# SCH_IMU_4connectors_antiCW.net
KiCad netlist of a schematic drawn in EasyEDA
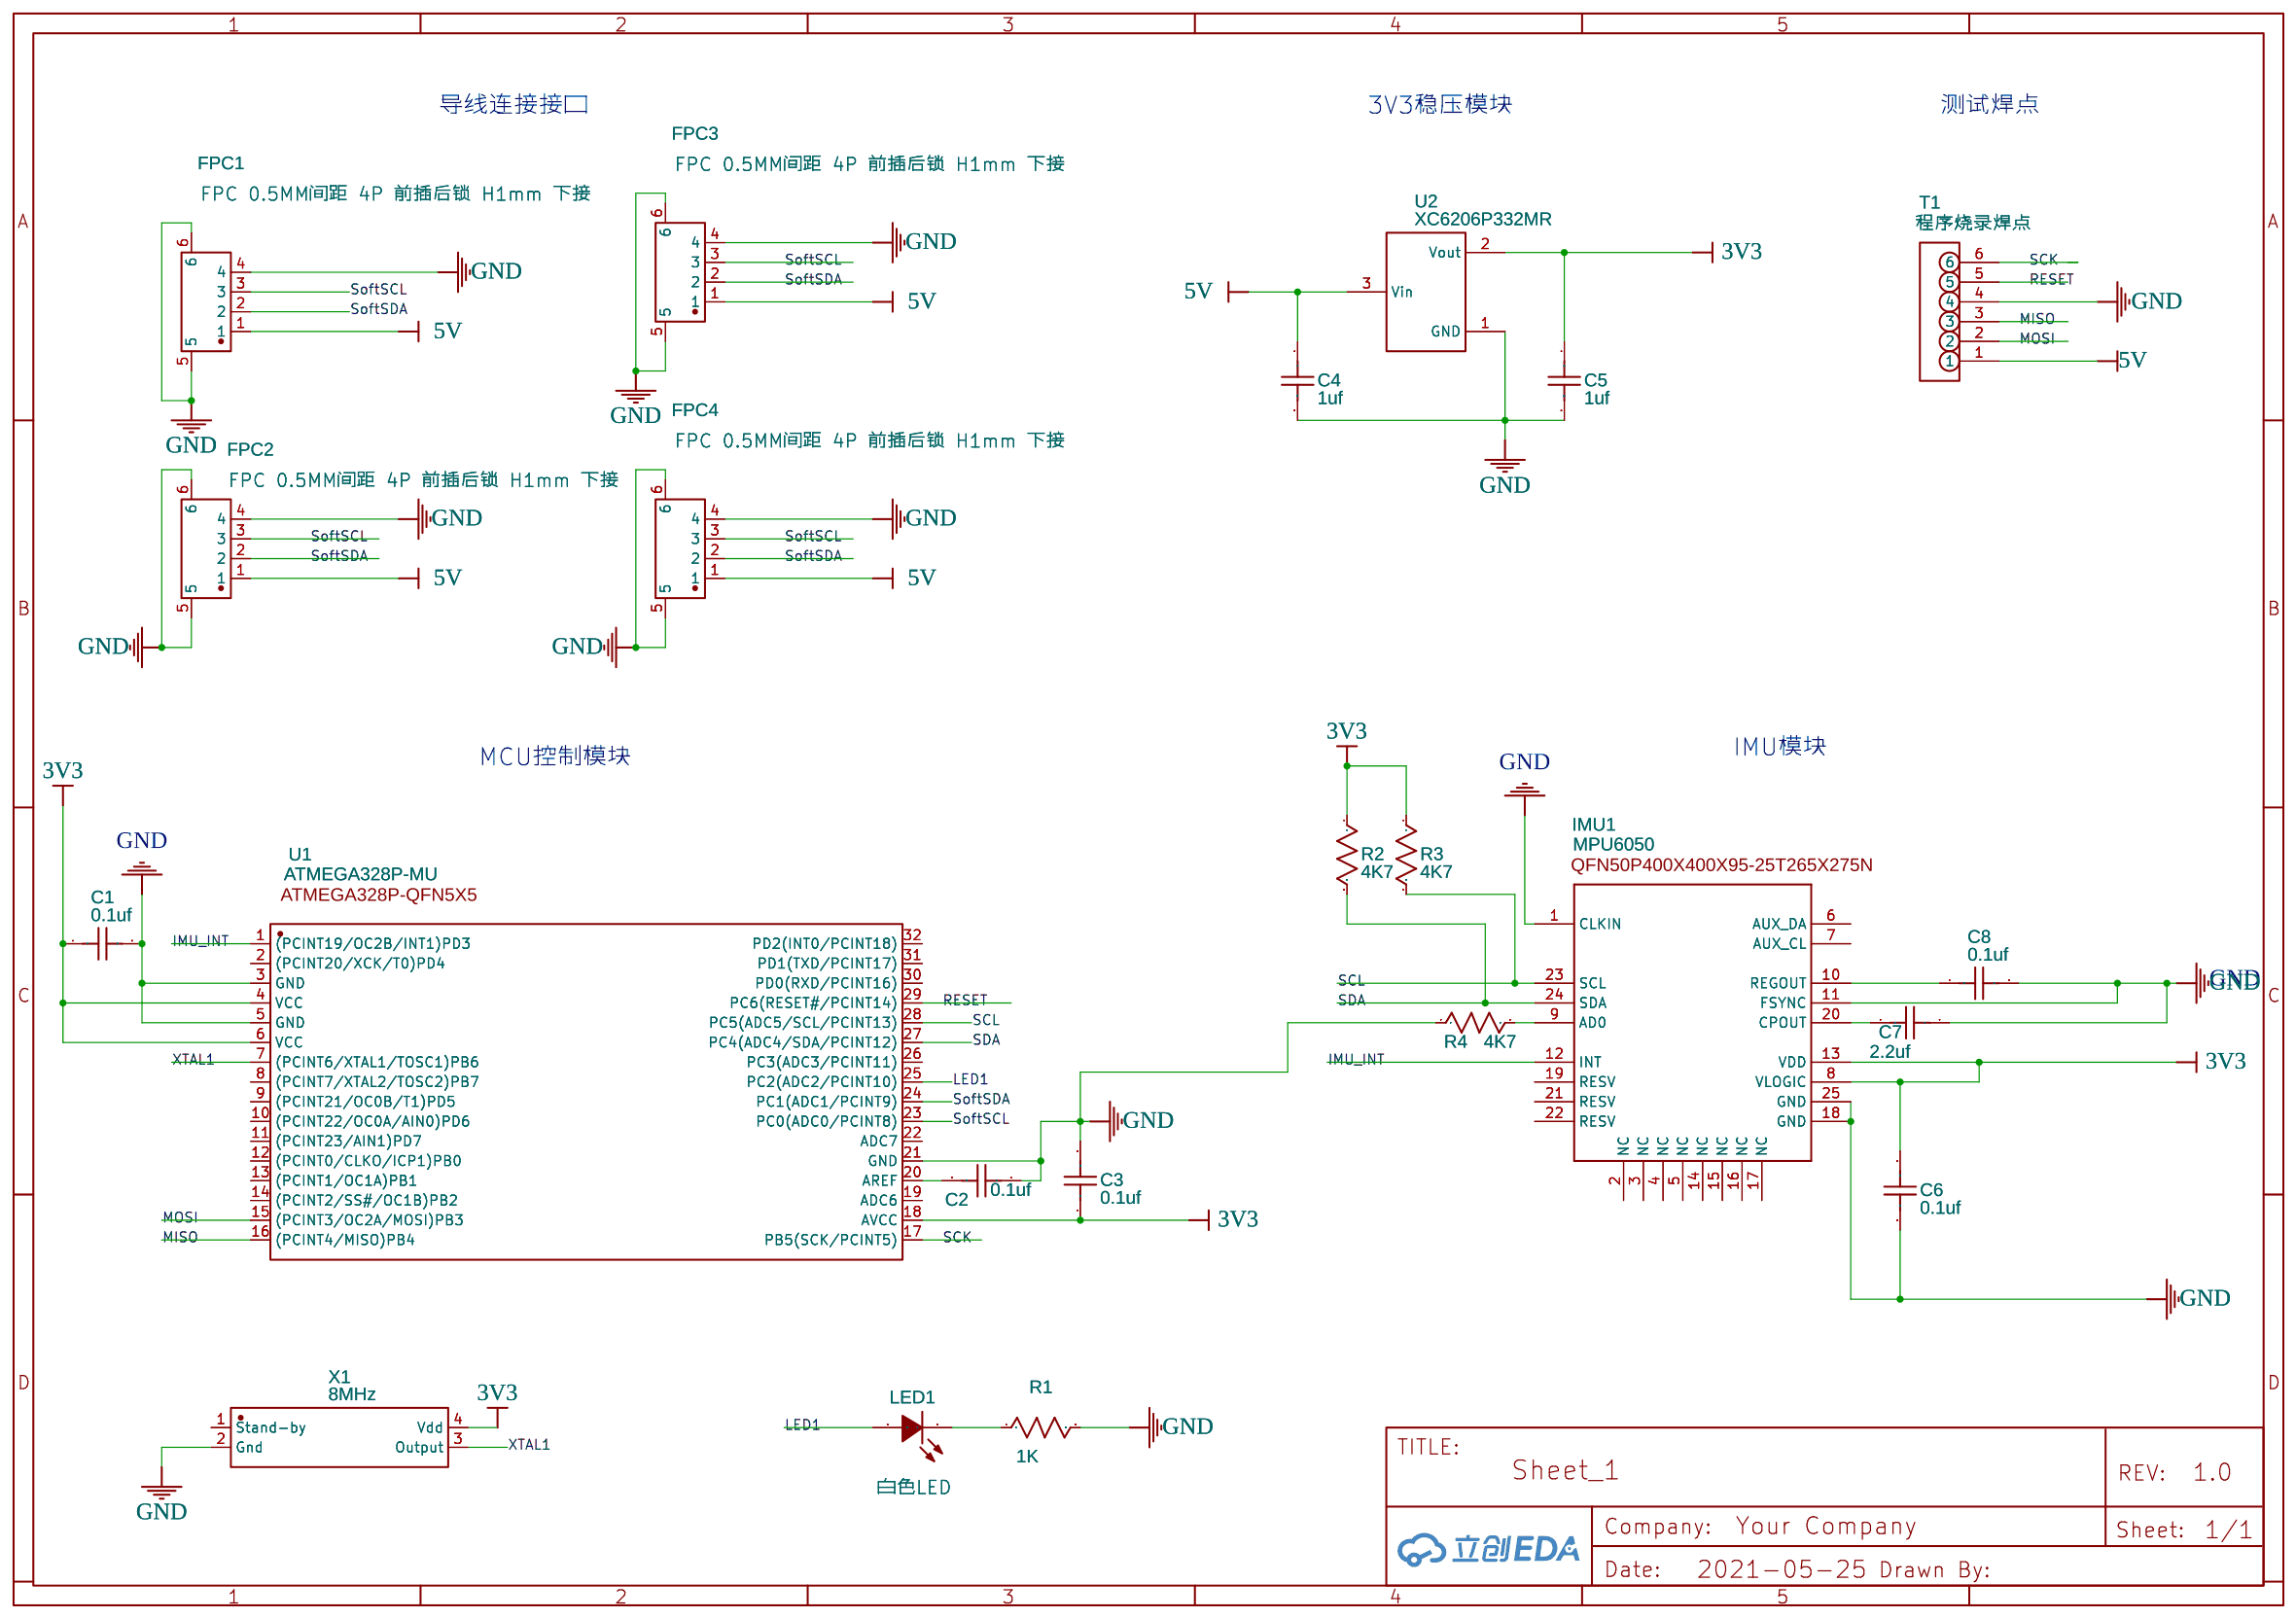
[diagram p0: schematic sheet]

(export (version "E")
  (design (tool "Eeschema 10.0.6"))
  (components
    (comp (ref "C1") (value "0.1uf") (libsource (lib "") (part "C_0402_US_2")))
    (comp (ref "C2") (value "0.1uf") (libsource (lib "") (part "C_0402_US_1")))
    (comp (ref "C3") (value "0.1uf") (libsource (lib "") (part "C_0402_US_3")))
    (comp (ref "C4") (value "1uf") (libsource (lib "") (part "C_0402_US")))
    (comp (ref "C5") (value "1uf") (libsource (lib "") (part "C_0402_US")))
    (comp (ref "C6") (value "0.1uf") (libsource (lib "") (part "C_0402_US")))
    (comp (ref "C7") (value "2.2uf") (libsource (lib "") (part "C_0402_US_1")))
    (comp (ref "C8") (value "0.1uf") (libsource (lib "") (part "C_0402_US_2")))
    (comp (ref "FPC1")
      (value "FPC 0.5MM间距 4P 前插后锁 H1mm 下接")
      (fields
        (field (name "BOM_Manufacturer Part") "FPC 0.5MM 4P 翻盖式 H2.0")
        (field (name "BOM_Supplier Part") "C9345")
      )
      (libsource (lib "") (part "FPC 0.5MM 4P 翻盖式 H2.0"))
    )
    (comp (ref "FPC2")
      (value "FPC 0.5MM间距 4P 前插后锁 H1mm 下接")
      (fields
        (field (name "BOM_Manufacturer Part") "FPC 0.5MM 4P 翻盖式 H2.0")
        (field (name "BOM_Supplier Part") "C9345")
      )
      (libsource (lib "") (part "FPC 0.5MM 4P 翻盖式 H2.0"))
    )
    (comp (ref "FPC3")
      (value "FPC 0.5MM间距 4P 前插后锁 H1mm 下接")
      (fields
        (field (name "BOM_Manufacturer Part") "FPC 0.5MM 4P 翻盖式 H2.0")
        (field (name "BOM_Supplier Part") "C9345")
      )
      (libsource (lib "") (part "FPC 0.5MM 4P 翻盖式 H2.0"))
    )
    (comp (ref "FPC4")
      (value "FPC 0.5MM间距 4P 前插后锁 H1mm 下接")
      (fields
        (field (name "BOM_Manufacturer Part") "FPC 0.5MM 4P 翻盖式 H2.0")
        (field (name "BOM_Supplier Part") "C9345")
      )
      (libsource (lib "") (part "FPC 0.5MM 4P 翻盖式 H2.0"))
    )
    (comp (ref "IMU1") (value "MPU6050") (libsource (lib "") (part "MPU6050")))
    (comp (ref "LED1")
      (value "白色LED")
      (fields
        (field (name "BOM_Manufacturer Part") "19-217/BHC-XL2M2TY/3T")
        (field (name "BOM_Supplier Part") "C264464")
      )
      (libsource (lib "") (part "19-217/BHC-XL2M2TY/3T"))
    )
    (comp (ref "R1") (value "1K") (libsource (lib "") (part "R_0402_US_1")))
    (comp (ref "R2") (value "4K7") (libsource (lib "") (part "R_0402_US")))
    (comp (ref "R3") (value "4K7") (libsource (lib "") (part "R_0402_US")))
    (comp (ref "R4") (value "4K7") (libsource (lib "") (part "R_0402_US_1")))
    (comp (ref "T1") (value "程序烧录焊点") (libsource (lib "") (part "Test")))
    (comp (ref "U1")
      (value "ATMEGA328P-MU")
      (fields
        (field (name "BOM_Manufacturer Part") "ATMEGA328P-AU")
        (field (name "BOM_Supplier Part") "C14877")
      )
      (libsource (lib "") (part "ATMEGA328P-AU"))
    )
    (comp (ref "U2")
      (value "XC6206P332MR")
      (fields (field (name "BOM_Supplier Part") "C5446"))
      (libsource (lib "") (part "XC6206P332MR"))
    )
    (comp (ref "X1")
      (value "8MHz")
      (fields
        (field (name "BOM_Manufacturer Part") "ECS-1612MV-080-CN-TR")
        (field (name "BOM_Supplier Part") "C405436")
      )
      (libsource (lib "") (part "ECS-1612MV-080-CN-TR"))
    )
  )
  (nets
    (net (code "1") (name "/IMU_INT") (class "Default")
      (node (ref "IMU1") (pin "12") (pinfunction "INT_12") (pintype "unspecified"))
      (node (ref "U1") (pin "1") (pinfunction "(PCINT19/OC2B/INT1)PD3_1") (pintype "unspecified"))
    )
    (net (code "2") (name "/LED1") (class "Default")
      (node (ref "LED1") (pin "1") (pinfunction "A_1") (pintype "unspecified"))
      (node (ref "U1") (pin "25") (pinfunction "PC2(ADC2/PCINT10)_25") (pintype "unspecified"))
    )
    (net (code "3") (name "/MISO") (class "Default")
      (node (ref "T1") (pin "3") (pinfunction "3_3") (pintype "unspecified"))
      (node (ref "U1") (pin "16") (pinfunction "(PCINT4/MISO)PB4_16") (pintype "unspecified"))
    )
    (net (code "4") (name "/MOSI") (class "Default")
      (node (ref "T1") (pin "2") (pinfunction "2_2") (pintype "unspecified"))
      (node (ref "U1") (pin "15") (pinfunction "(PCINT3/OC2A/MOSI)PB3_15") (pintype "unspecified"))
    )
    (net (code "5") (name "/RESET") (class "Default")
      (node (ref "T1") (pin "5") (pinfunction "5_5") (pintype "unspecified"))
      (node (ref "U1") (pin "29") (pinfunction "PC6(RESET#/PCINT14)_29") (pintype "unspecified"))
    )
    (net (code "6") (name "/SCK") (class "Default")
      (node (ref "T1") (pin "6") (pinfunction "6_6") (pintype "unspecified"))
      (node (ref "U1") (pin "17") (pinfunction "PB5(SCK/PCINT5)_17") (pintype "unspecified"))
    )
    (net (code "7") (name "/SCL") (class "Default")
      (node (ref "IMU1") (pin "23") (pinfunction "SCL_23") (pintype "input"))
      (node (ref "R3") (pin "2") (pinfunction "2_2") (pintype "unspecified"))
      (node (ref "U1") (pin "28") (pinfunction "PC5(ADC5/SCL/PCINT13)_28") (pintype "unspecified"))
    )
    (net (code "8") (name "/SDA") (class "Default")
      (node (ref "IMU1") (pin "24") (pinfunction "SDA_24") (pintype "unspecified"))
      (node (ref "R2") (pin "2") (pinfunction "2_2") (pintype "unspecified"))
      (node (ref "U1") (pin "27") (pinfunction "PC4(ADC4/SDA/PCINT12)_27") (pintype "unspecified"))
    )
    (net (code "9") (name "/SoftSCL") (class "Default")
      (node (ref "FPC1") (pin "3") (pinfunction "3_3") (pintype "unspecified"))
      (node (ref "FPC2") (pin "3") (pinfunction "3_3") (pintype "unspecified"))
      (node (ref "FPC3") (pin "3") (pinfunction "3_3") (pintype "unspecified"))
      (node (ref "FPC4") (pin "3") (pinfunction "3_3") (pintype "unspecified"))
      (node (ref "U1") (pin "23") (pinfunction "PC0(ADC0/PCINT8)_23") (pintype "unspecified"))
    )
    (net (code "10") (name "/SoftSDA") (class "Default")
      (node (ref "FPC1") (pin "2") (pinfunction "2_2") (pintype "unspecified"))
      (node (ref "FPC2") (pin "2") (pinfunction "2_2") (pintype "unspecified"))
      (node (ref "FPC3") (pin "2") (pinfunction "2_2") (pintype "unspecified"))
      (node (ref "FPC4") (pin "2") (pinfunction "2_2") (pintype "unspecified"))
      (node (ref "U1") (pin "24") (pinfunction "PC1(ADC1/PCINT9)_24") (pintype "unspecified"))
    )
    (net (code "11") (name "/XTAL1") (class "Default")
      (node (ref "U1") (pin "7") (pinfunction "(PCINT6/XTAL1/TOSC1)PB6_7") (pintype "unspecified"))
      (node (ref "X1") (pin "3") (pinfunction "Output_3") (pintype "unspecified"))
    )
    (net (code "12") (name "3V3") (class "Default")
      (node (ref "C1") (pin "1") (pinfunction "1_1") (pintype "unspecified"))
      (node (ref "C3") (pin "1") (pinfunction "1_1") (pintype "unspecified"))
      (node (ref "C5") (pin "1") (pinfunction "1_1") (pintype "unspecified"))
      (node (ref "C6") (pin "1") (pinfunction "1_1") (pintype "unspecified"))
      (node (ref "IMU1") (pin "13") (pinfunction "VDD_13") (pintype "passive"))
      (node (ref "IMU1") (pin "8") (pinfunction "VLOGIC_8") (pintype "passive"))
      (node (ref "R2") (pin "1") (pinfunction "1_1") (pintype "unspecified"))
      (node (ref "R3") (pin "1") (pinfunction "1_1") (pintype "unspecified"))
      (node (ref "U1") (pin "18") (pinfunction "AVCC_18") (pintype "unspecified"))
      (node (ref "U1") (pin "4") (pinfunction "VCC_4") (pintype "unspecified"))
      (node (ref "U1") (pin "6") (pinfunction "VCC_6") (pintype "unspecified"))
      (node (ref "U2") (pin "2") (pinfunction "Vout_2") (pintype "unspecified"))
      (node (ref "X1") (pin "4") (pinfunction "Vdd_4") (pintype "unspecified"))
    )
    (net (code "13") (name "5V") (class "Default")
      (node (ref "C4") (pin "1") (pinfunction "1_1") (pintype "unspecified"))
      (node (ref "FPC1") (pin "1") (pinfunction "1_1") (pintype "unspecified"))
      (node (ref "FPC2") (pin "1") (pinfunction "1_1") (pintype "unspecified"))
      (node (ref "FPC3") (pin "1") (pinfunction "1_1") (pintype "unspecified"))
      (node (ref "FPC4") (pin "1") (pinfunction "1_1") (pintype "unspecified"))
      (node (ref "T1") (pin "1") (pinfunction "1_1") (pintype "unspecified"))
      (node (ref "U2") (pin "3") (pinfunction "Vin_3") (pintype "unspecified"))
    )
    (net (code "14") (name "GND") (class "Default")
      (node (ref "C1") (pin "2") (pinfunction "2_2") (pintype "unspecified"))
      (node (ref "C2") (pin "1") (pinfunction "1_1") (pintype "unspecified"))
      (node (ref "C3") (pin "2") (pinfunction "2_2") (pintype "unspecified"))
      (node (ref "C4") (pin "2") (pinfunction "2_2") (pintype "unspecified"))
      (node (ref "C5") (pin "2") (pinfunction "2_2") (pintype "unspecified"))
      (node (ref "C6") (pin "2") (pinfunction "2_2") (pintype "unspecified"))
      (node (ref "C7") (pin "1") (pinfunction "1_1") (pintype "unspecified"))
      (node (ref "C8") (pin "2") (pinfunction "2_2") (pintype "unspecified"))
      (node (ref "FPC1") (pin "4") (pinfunction "4_4") (pintype "unspecified"))
      (node (ref "FPC1") (pin "5") (pinfunction "5_5") (pintype "unspecified"))
      (node (ref "FPC1") (pin "6") (pinfunction "6_6") (pintype "unspecified"))
      (node (ref "FPC2") (pin "4") (pinfunction "4_4") (pintype "unspecified"))
      (node (ref "FPC2") (pin "5") (pinfunction "5_5") (pintype "unspecified"))
      (node (ref "FPC2") (pin "6") (pinfunction "6_6") (pintype "unspecified"))
      (node (ref "FPC3") (pin "4") (pinfunction "4_4") (pintype "unspecified"))
      (node (ref "FPC3") (pin "5") (pinfunction "5_5") (pintype "unspecified"))
      (node (ref "FPC3") (pin "6") (pinfunction "6_6") (pintype "unspecified"))
      (node (ref "FPC4") (pin "4") (pinfunction "4_4") (pintype "unspecified"))
      (node (ref "FPC4") (pin "5") (pinfunction "5_5") (pintype "unspecified"))
      (node (ref "FPC4") (pin "6") (pinfunction "6_6") (pintype "unspecified"))
      (node (ref "IMU1") (pin "1") (pinfunction "CLKIN_1") (pintype "input"))
      (node (ref "IMU1") (pin "11") (pinfunction "FSYNC_11") (pintype "input"))
      (node (ref "IMU1") (pin "18") (pinfunction "GND_18") (pintype "passive"))
      (node (ref "IMU1") (pin "25") (pinfunction "GND_25") (pintype "passive"))
      (node (ref "R1") (pin "2") (pinfunction "2_2") (pintype "unspecified"))
      (node (ref "R4") (pin "1") (pinfunction "1_1") (pintype "unspecified"))
      (node (ref "T1") (pin "4") (pinfunction "4_4") (pintype "unspecified"))
      (node (ref "U1") (pin "21") (pinfunction "GND_21") (pintype "unspecified"))
      (node (ref "U1") (pin "3") (pinfunction "GND_3") (pintype "unspecified"))
      (node (ref "U1") (pin "5") (pinfunction "GND_5") (pintype "unspecified"))
      (node (ref "U2") (pin "1") (pinfunction "GND_1") (pintype "unspecified"))
      (node (ref "X1") (pin "2") (pinfunction "Gnd_2") (pintype "unspecified"))
    )
    (net (code "15") (name "Net-(IMU1-AD0)") (class "Default")
      (node (ref "IMU1") (pin "9") (pinfunction "AD0_9") (pintype "input"))
      (node (ref "R4") (pin "2") (pinfunction "2_2") (pintype "unspecified"))
    )
    (net (code "16") (name "Net-(IMU1-CPOUT)") (class "Default")
      (node (ref "C7") (pin "2") (pinfunction "2_2") (pintype "unspecified"))
      (node (ref "IMU1") (pin "20") (pinfunction "CPOUT_20") (pintype "output"))
    )
    (net (code "17") (name "Net-(IMU1-REGOUT)") (class "Default")
      (node (ref "C8") (pin "1") (pinfunction "1_1") (pintype "unspecified"))
      (node (ref "IMU1") (pin "10") (pinfunction "REGOUT_10") (pintype "output"))
    )
    (net (code "18") (name "Net-(LED1-K)") (class "Default")
      (node (ref "LED1") (pin "2") (pinfunction "K_2") (pintype "unspecified"))
      (node (ref "R1") (pin "1") (pinfunction "1_1") (pintype "unspecified"))
    )
    (net (code "19") (name "Net-(U1-AREF)") (class "Default")
      (node (ref "C2") (pin "2") (pinfunction "2_2") (pintype "unspecified"))
      (node (ref "U1") (pin "20") (pinfunction "AREF_20") (pintype "unspecified"))
    )
    (net (code "20") (name "unconnected-(IMU1-AUX_CL-Pad7)") (class "Default")
      (node (ref "IMU1") (pin "7") (pinfunction "AUX_CL_7") (pintype "unspecified"))
    )
    (net (code "21") (name "unconnected-(IMU1-AUX_DA-Pad6)") (class "Default")
      (node (ref "IMU1") (pin "6") (pinfunction "AUX_DA_6") (pintype "unspecified"))
    )
    (net (code "22") (name "unconnected-(IMU1-NC-Pad2)") (class "Default")
      (node (ref "IMU1") (pin "2") (pinfunction "NC_2") (pintype "unspecified"))
    )
    (net (code "23") (name "unconnected-(IMU1-NC-Pad3)") (class "Default")
      (node (ref "IMU1") (pin "3") (pinfunction "NC_3") (pintype "unspecified"))
    )
    (net (code "24") (name "unconnected-(IMU1-NC-Pad4)") (class "Default")
      (node (ref "IMU1") (pin "4") (pinfunction "NC_4") (pintype "unspecified"))
    )
    (net (code "25") (name "unconnected-(IMU1-NC-Pad5)") (class "Default")
      (node (ref "IMU1") (pin "5") (pinfunction "NC_5") (pintype "unspecified"))
    )
    (net (code "26") (name "unconnected-(IMU1-NC-Pad14)") (class "Default")
      (node (ref "IMU1") (pin "14") (pinfunction "NC_14") (pintype "unspecified"))
    )
    (net (code "27") (name "unconnected-(IMU1-NC-Pad15)") (class "Default")
      (node (ref "IMU1") (pin "15") (pinfunction "NC_15") (pintype "unspecified"))
    )
    (net (code "28") (name "unconnected-(IMU1-NC-Pad16)") (class "Default")
      (node (ref "IMU1") (pin "16") (pinfunction "NC_16") (pintype "unspecified"))
    )
    (net (code "29") (name "unconnected-(IMU1-NC-Pad17)") (class "Default")
      (node (ref "IMU1") (pin "17") (pinfunction "NC_17") (pintype "unspecified"))
    )
    (net (code "30") (name "unconnected-(IMU1-RESV-Pad19)") (class "Default")
      (node (ref "IMU1") (pin "19") (pinfunction "RESV_19") (pintype "unspecified"))
    )
    (net (code "31") (name "unconnected-(IMU1-RESV-Pad21)") (class "Default")
      (node (ref "IMU1") (pin "21") (pinfunction "RESV_21") (pintype "unspecified"))
    )
    (net (code "32") (name "unconnected-(IMU1-RESV-Pad22)") (class "Default")
      (node (ref "IMU1") (pin "22") (pinfunction "RESV_22") (pintype "unspecified"))
    )
    (net (code "33") (name "unconnected-(U1-(PCINT0{slash}CLKO{slash}ICP1)PB0-Pad12)") (class "Default")
      (node (ref "U1") (pin "12") (pinfunction "(PCINT0/CLKO/ICP1)PB0_12") (pintype "unspecified"))
    )
    (net (code "34") (name "unconnected-(U1-(PCINT1{slash}OC1A)PB1-Pad13)") (class "Default")
      (node (ref "U1") (pin "13") (pinfunction "(PCINT1/OC1A)PB1_13") (pintype "unspecified"))
    )
    (net (code "35") (name "unconnected-(U1-(PCINT2{slash}SS#{slash}OC1B)PB2-Pad14)") (class "Default")
      (node (ref "U1") (pin "14") (pinfunction "(PCINT2/SS#/OC1B)PB2_14") (pintype "unspecified"))
    )
    (net (code "36") (name "unconnected-(U1-(PCINT7{slash}XTAL2{slash}TOSC2)PB7-Pad8)") (class "Default")
      (node (ref "U1") (pin "8") (pinfunction "(PCINT7/XTAL2/TOSC2)PB7_8") (pintype "unspecified"))
    )
    (net (code "37") (name "unconnected-(U1-(PCINT20{slash}XCK{slash}T0)PD4-Pad2)") (class "Default")
      (node (ref "U1") (pin "2") (pinfunction "(PCINT20/XCK/T0)PD4_2") (pintype "unspecified"))
    )
    (net (code "38") (name "unconnected-(U1-(PCINT21{slash}OC0B{slash}T1)PD5-Pad9)") (class "Default")
      (node (ref "U1") (pin "9") (pinfunction "(PCINT21/OC0B/T1)PD5_9") (pintype "unspecified"))
    )
    (net (code "39") (name "unconnected-(U1-(PCINT22{slash}OC0A{slash}AIN0)PD6-Pad10)") (class "Default")
      (node (ref "U1") (pin "10") (pinfunction "(PCINT22/OC0A/AIN0)PD6_10") (pintype "unspecified"))
    )
    (net (code "40") (name "unconnected-(U1-(PCINT23{slash}AIN1)PD7-Pad11)") (class "Default")
      (node (ref "U1") (pin "11") (pinfunction "(PCINT23/AIN1)PD7_11") (pintype "unspecified"))
    )
    (net (code "41") (name "unconnected-(U1-ADC6-Pad19)") (class "Default")
      (node (ref "U1") (pin "19") (pinfunction "ADC6_19") (pintype "unspecified"))
    )
    (net (code "42") (name "unconnected-(U1-ADC7-Pad22)") (class "Default")
      (node (ref "U1") (pin "22") (pinfunction "ADC7_22") (pintype "unspecified"))
    )
    (net (code "43") (name "unconnected-(U1-PC3(ADC3{slash}PCINT11)-Pad26)") (class "Default")
      (node (ref "U1") (pin "26") (pinfunction "PC3(ADC3/PCINT11)_26") (pintype "unspecified"))
    )
    (net (code "44") (name "unconnected-(U1-PD0(RXD{slash}PCINT16)-Pad30)") (class "Default")
      (node (ref "U1") (pin "30") (pinfunction "PD0(RXD/PCINT16)_30") (pintype "unspecified"))
    )
    (net (code "45") (name "unconnected-(U1-PD1(TXD{slash}PCINT17)-Pad31)") (class "Default")
      (node (ref "U1") (pin "31") (pinfunction "PD1(TXD/PCINT17)_31") (pintype "unspecified"))
    )
    (net (code "46") (name "unconnected-(U1-PD2(INT0{slash}PCINT18)-Pad32)") (class "Default")
      (node (ref "U1") (pin "32") (pinfunction "PD2(INT0/PCINT18)_32") (pintype "unspecified"))
    )
    (net (code "47") (name "unconnected-(X1-Stand-by-Pad1)") (class "Default")
      (node (ref "X1") (pin "1") (pinfunction "Stand-by_1") (pintype "unspecified"))
    )
  )
)
